# TDA7377.net
KiCad netlist of a schematic drawn in EAGLE
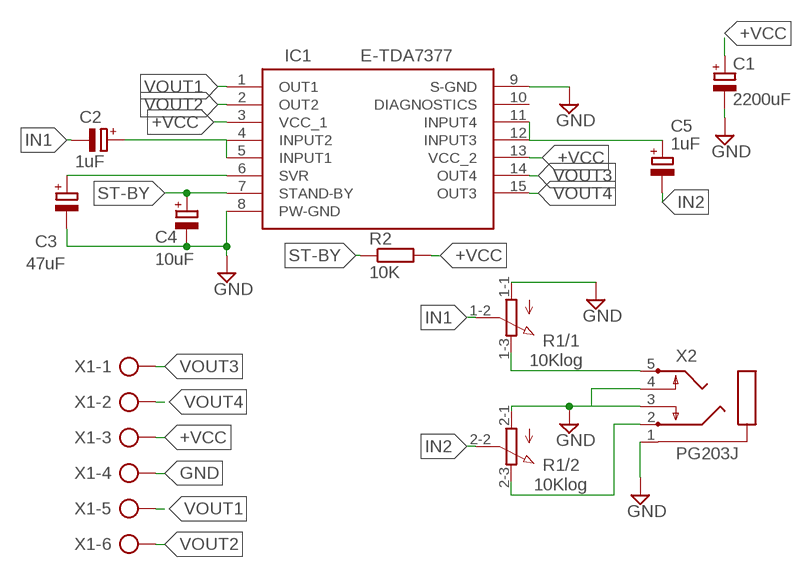
[diagram p0: schematic, sheet 1]

(export (version "E")
  (design (tool "Eeschema 10.0.6"))
  (components
    (comp (ref "C1")
      (value "2200uF")
      (footprint "eagle-import:E5-13")
      (libsource (lib "eagle-import") (part "CPOL-EUE5-13"))
    )
    (comp (ref "C2")
      (value "1uF")
      (footprint "eagle-import:E2,5-6")
      (libsource (lib "eagle-import") (part "CPOL-EUE2.5-6"))
    )
    (comp (ref "C3")
      (value "47uF")
      (footprint "eagle-import:E2,5-6")
      (libsource (lib "eagle-import") (part "CPOL-EUE2.5-6"))
    )
    (comp (ref "C4")
      (value "10uF")
      (footprint "eagle-import:E2,5-5")
      (libsource (lib "eagle-import") (part "CPOL-EUE2.5-5"))
    )
    (comp (ref "C5")
      (value "1uF")
      (footprint "eagle-import:E5-5")
      (libsource (lib "eagle-import") (part "CPOL-EUE5-5"))
    )
    (comp (ref "IC1")
      (value "E-TDA7377")
      (footprint "eagle-import:TO127P500X2020X2210-15P")
      (fields (field (name "MOUSER_PART_NUMBER") "511-E-TDA7377"))
      (libsource (lib "eagle-import") (part "E-TDA7377"))
    )
    (comp (ref "R1")
      (value "10Klog")
      (footprint "eagle-import:3RP_1610G")
      (libsource (lib "eagle-import") (part "3RP/1610G"))
    )
    (comp (ref "R2")
      (value "10K")
      (footprint "eagle-import:0207_10")
      (libsource (lib "eagle-import") (part "R-EU_0207/10"))
    )
    (comp (ref "X1")
      (value "AK500/6-H")
      (footprint "eagle-import:AK500_6-H")
      (libsource (lib "eagle-import") (part "AK500/6-H"))
    )
    (comp (ref "X2")
      (value "PG203J")
      (footprint "eagle-import:PG203J")
      (libsource (lib "eagle-import") (part "PG203J"))
    )
  )
  (nets
    (net (code "1") (name "+VCC") (class "Default")
      (node (ref "C1") (pin "+") (pinfunction "+_+") (pintype "passive"))
      (node (ref "IC1") (pin "13") (pinfunction "VCC_2_13") (pintype "bidirectional"))
      (node (ref "IC1") (pin "3") (pinfunction "VCC_1_3") (pintype "bidirectional"))
      (node (ref "R2") (pin "2") (pinfunction "2_2") (pintype "passive"))
      (node (ref "X1") (pin "3") (pinfunction "KL_3") (pintype "passive"))
    )
    (net (code "2") (name "GND") (class "Default")
      (node (ref "C1") (pin "-") (pinfunction "-_-") (pintype "passive"))
      (node (ref "C3") (pin "-") (pinfunction "-_-") (pintype "passive"))
      (node (ref "C4") (pin "-") (pinfunction "-_-") (pintype "passive"))
      (node (ref "IC1") (pin "8") (pinfunction "PW-GND_8") (pintype "bidirectional"))
      (node (ref "IC1") (pin "9") (pinfunction "S-GND_9") (pintype "bidirectional"))
      (node (ref "R1") (pin "1-1") (pinfunction "A_1-1") (pintype "passive"))
      (node (ref "R1") (pin "2-1") (pinfunction "A_2-1") (pintype "passive"))
      (node (ref "X1") (pin "4") (pinfunction "KL_4") (pintype "passive"))
      (node (ref "X2") (pin "1") (pinfunction "1_1") (pintype "passive"))
      (node (ref "X2") (pin "3") (pinfunction "3_3") (pintype "passive"))
      (node (ref "X2") (pin "4") (pinfunction "4_4") (pintype "passive"))
    )
    (net (code "3") (name "IN1") (class "Default")
      (node (ref "C2") (pin "-") (pinfunction "-_-") (pintype "passive"))
      (node (ref "R1") (pin "1-2") (pinfunction "S_1-2") (pintype "passive"))
    )
    (net (code "4") (name "IN2") (class "Default")
      (node (ref "C5") (pin "-") (pinfunction "-_-") (pintype "passive"))
      (node (ref "R1") (pin "2-2") (pinfunction "S_2-2") (pintype "passive"))
    )
    (net (code "5") (name "Net-(IC1-INPUT1)") (class "Default")
      (node (ref "C2") (pin "+") (pinfunction "+_+") (pintype "passive"))
      (node (ref "IC1") (pin "4") (pinfunction "INPUT2_4") (pintype "bidirectional"))
      (node (ref "IC1") (pin "5") (pinfunction "INPUT1_5") (pintype "bidirectional"))
    )
    (net (code "6") (name "Net-(IC1-INPUT3)") (class "Default")
      (node (ref "C5") (pin "+") (pinfunction "+_+") (pintype "passive"))
      (node (ref "IC1") (pin "11") (pinfunction "INPUT4_11") (pintype "bidirectional"))
      (node (ref "IC1") (pin "12") (pinfunction "INPUT3_12") (pintype "bidirectional"))
    )
    (net (code "7") (name "Net-(IC1-SVR)") (class "Default")
      (node (ref "C3") (pin "+") (pinfunction "+_+") (pintype "passive"))
      (node (ref "IC1") (pin "6") (pinfunction "SVR_6") (pintype "bidirectional"))
    )
    (net (code "8") (name "Net-(R1A-E)") (class "Default")
      (node (ref "R1") (pin "1-3") (pinfunction "E_1-3") (pintype "passive"))
      (node (ref "X2") (pin "5") (pinfunction "5_5") (pintype "passive"))
    )
    (net (code "9") (name "Net-(R1B-E)") (class "Default")
      (node (ref "R1") (pin "2-3") (pinfunction "E_2-3") (pintype "passive"))
      (node (ref "X2") (pin "2") (pinfunction "2_2") (pintype "passive"))
    )
    (net (code "10") (name "ST-BY") (class "Default")
      (node (ref "C4") (pin "+") (pinfunction "+_+") (pintype "passive"))
      (node (ref "IC1") (pin "7") (pinfunction "STAND-BY_7") (pintype "bidirectional"))
      (node (ref "R2") (pin "1") (pinfunction "1_1") (pintype "passive"))
    )
    (net (code "11") (name "VOUT1") (class "Default")
      (node (ref "IC1") (pin "1") (pinfunction "OUT1_1") (pintype "bidirectional"))
      (node (ref "X1") (pin "5") (pinfunction "KL_5") (pintype "passive"))
    )
    (net (code "12") (name "VOUT2") (class "Default")
      (node (ref "IC1") (pin "2") (pinfunction "OUT2_2") (pintype "bidirectional"))
      (node (ref "X1") (pin "6") (pinfunction "KL_6") (pintype "passive"))
    )
    (net (code "13") (name "VOUT3") (class "Default")
      (node (ref "IC1") (pin "14") (pinfunction "OUT4_14") (pintype "bidirectional"))
      (node (ref "X1") (pin "1") (pinfunction "KL_1") (pintype "passive"))
    )
    (net (code "14") (name "VOUT4") (class "Default")
      (node (ref "IC1") (pin "15") (pinfunction "OUT3_15") (pintype "bidirectional"))
      (node (ref "X1") (pin "2") (pinfunction "KL_2") (pintype "passive"))
    )
    (net (code "15") (name "unconnected-(IC1-DIAGNOSTICS-Pad10)") (class "Default")
      (node (ref "IC1") (pin "10") (pinfunction "DIAGNOSTICS_10") (pintype "bidirectional"))
    )
  )
)
